# SCH-8-ESC6.net
KiCad netlist of a schematic drawn in Altium Designer
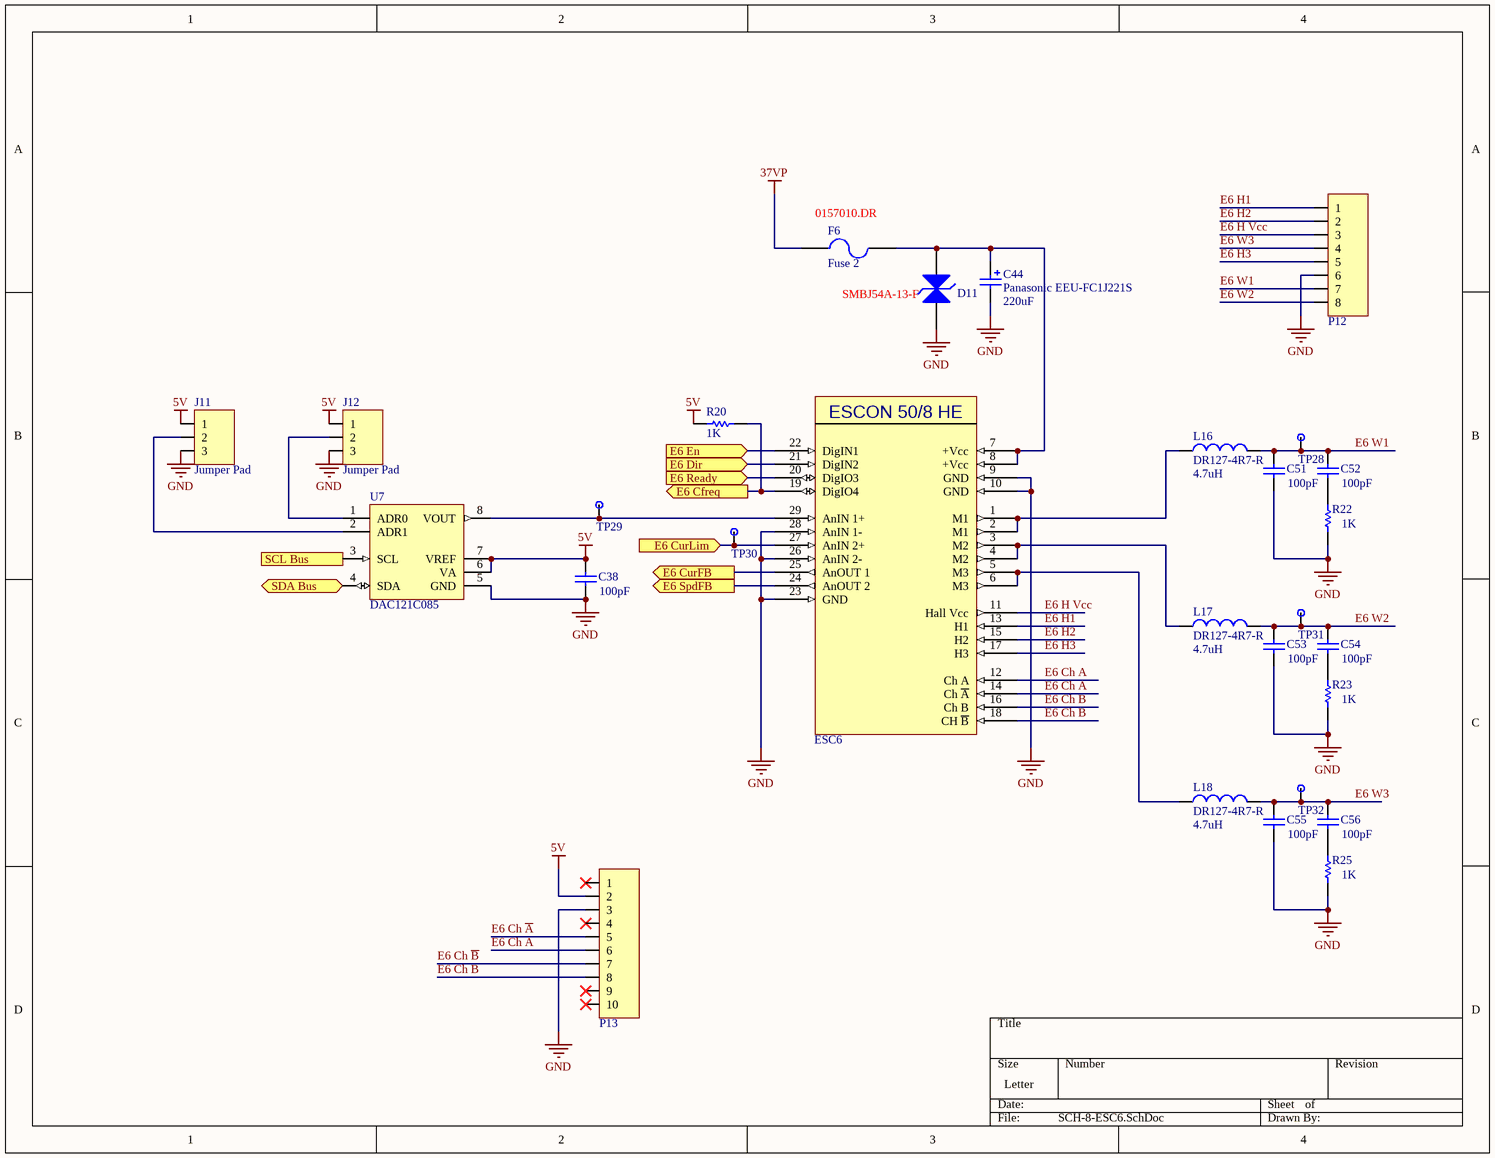
[diagram p0: SCH-8-ESC6.SchDoc]

(export (version "E")
  (design (tool "Eeschema 10.0.6"))
  (components
    (comp (ref "C38")
      (value "100pF")
      (footprint "C1206")
      (description "Capacitor (Semiconductor SIM Model)")
      (fields (field (name "Comment") "Cap Semi") (field (name "PUBLISHER") "Altium Limited"))
      (libsource (lib "Miscellaneous Devices") (part "Cap Semi"))
    )
    (comp (ref "C44")
      (value "Panasonic EEU-FC1J221S")
      (footprint "Panasonic EEU-FC1J221S")
      (description "Polarized Capacitor (Radial)")
      (fields (field (name "ALTIUM_VALUE") "220uF"))
      (libsource (lib "RSX_Capacitors") (part "Panasonic EEU-FC1J221S"))
    )
    (comp (ref "C51")
      (value "100pF")
      (footprint "C1206")
      (description "Capacitor (Semiconductor SIM Model)")
      (fields (field (name "Comment") "Cap Semi") (field (name "PUBLISHER") "Altium Limited"))
      (libsource (lib "Miscellaneous Devices") (part "Cap Semi"))
    )
    (comp (ref "C52")
      (value "100pF")
      (footprint "C1206")
      (description "Capacitor (Semiconductor SIM Model)")
      (fields (field (name "Comment") "Cap Semi") (field (name "PUBLISHER") "Altium Limited"))
      (libsource (lib "Miscellaneous Devices") (part "Cap Semi"))
    )
    (comp (ref "C53")
      (value "100pF")
      (footprint "C1206")
      (description "Capacitor (Semiconductor SIM Model)")
      (fields (field (name "Comment") "Cap Semi") (field (name "PUBLISHER") "Altium Limited"))
      (libsource (lib "Miscellaneous Devices") (part "Cap Semi"))
    )
    (comp (ref "C54")
      (value "100pF")
      (footprint "C1206")
      (description "Capacitor (Semiconductor SIM Model)")
      (fields (field (name "Comment") "Cap Semi") (field (name "PUBLISHER") "Altium Limited"))
      (libsource (lib "Miscellaneous Devices") (part "Cap Semi"))
    )
    (comp (ref "C55")
      (value "100pF")
      (footprint "C1206")
      (description "Capacitor (Semiconductor SIM Model)")
      (fields (field (name "Comment") "Cap Semi") (field (name "PUBLISHER") "Altium Limited"))
      (libsource (lib "Miscellaneous Devices") (part "Cap Semi"))
    )
    (comp (ref "C56")
      (value "100pF")
      (footprint "C1206")
      (description "Capacitor (Semiconductor SIM Model)")
      (fields (field (name "Comment") "Cap Semi") (field (name "PUBLISHER") "Altium Limited"))
      (libsource (lib "Miscellaneous Devices") (part "Cap Semi"))
    )
    (comp (ref "D11")
      (value "TVS_DIODE")
      (footprint "SMBJ54A-13-F")
      (description "TVS Diode")
      (fields (field (name "PUBLISHER") "Altium Limited"))
      (libsource (lib "RSX_Diodes") (part "TVS_DIODE"))
    )
    (comp (ref "ESC6")
      (value "ESCON 50/8 HE")
      (footprint "ESCON 50/8 HE")
      (description "ESCON Module 50/8 HE Servocontroller")
      (libsource (lib "RSX_Modules") (part "ESCON 50/8 HE"))
    )
    (comp (ref "F6")
      (value "Fuse 2")
      (footprint "0157010.DR")
      (description "Fuse")
      (fields (field (name "PUBLISHER") "Altium Limited"))
      (libsource (lib "RSX_Miscellaneous") (part "Fuse 2"))
    )
    (comp (ref "J11")
      (value "Jumper Pad")
      (footprint "3 Pad TH")
      (libsource (lib "RSX_Test_Points") (part "3 Pad Jump Sel"))
    )
    (comp (ref "J12")
      (value "Jumper Pad")
      (footprint "3 Pad TH")
      (libsource (lib "RSX_Test_Points") (part "3 Pad Jump Sel"))
    )
    (comp (ref "L16")
      (value "DR127-4R7-R")
      (footprint "DR127-4R7-R")
      (description "4.7µH Shielded Wirewound Inductor 8.25A 9.17mOhm Nonstandard")
      (fields (field (name "ALTIUM_VALUE") "4.7uH") (field (name "PUBLISHER") "Altium Limited"))
      (libsource (lib "RSX_Inductors") (part "DR127-4R7-R"))
    )
    (comp (ref "L17")
      (value "DR127-4R7-R")
      (footprint "DR127-4R7-R")
      (description "4.7µH Shielded Wirewound Inductor 8.25A 9.17mOhm Nonstandard")
      (fields (field (name "ALTIUM_VALUE") "4.7uH") (field (name "PUBLISHER") "Altium Limited"))
      (libsource (lib "RSX_Inductors") (part "DR127-4R7-R"))
    )
    (comp (ref "L18")
      (value "DR127-4R7-R")
      (footprint "DR127-4R7-R")
      (description "4.7µH Shielded Wirewound Inductor 8.25A 9.17mOhm Nonstandard")
      (fields (field (name "ALTIUM_VALUE") "4.7uH") (field (name "PUBLISHER") "Altium Limited"))
      (libsource (lib "RSX_Inductors") (part "DR127-4R7-R"))
    )
    (comp (ref "P12")
      (value "Mini-Fit Jr 8 Pos")
      (footprint "Molex Mini-Fit Jr 0039281083")
      (libsource (lib "RSX_Connectors") (part "Molex Mini-Fit Jr 8pos Vert"))
    )
    (comp (ref "P13")
      (value "Header_10_Pos_Ribbon Male")
      (footprint "3M_2510-6002UB")
      (description "3M_2510-6002UB")
      (libsource (lib "RSX_Connectors") (part "Header_10_Pos_Ribbon Male"))
    )
    (comp (ref "R20")
      (value "1K")
      (footprint "RESC1608X06N_0603")
      (description "Resistor")
      (fields (field (name "Comment") "Res1") (field (name "PUBLISHER") "Altium Limited"))
      (libsource (lib "RSX_Resistors") (part "Res1"))
    )
    (comp (ref "R22")
      (value "1K")
      (footprint "RESC1608X06N_0603")
      (description "Resistor")
      (fields (field (name "Comment") "Res1") (field (name "PUBLISHER") "Altium Limited"))
      (libsource (lib "RSX_Resistors") (part "Res1"))
    )
    (comp (ref "R23")
      (value "1K")
      (footprint "RESC1608X06N_0603")
      (description "Resistor")
      (fields (field (name "Comment") "Res1") (field (name "PUBLISHER") "Altium Limited"))
      (libsource (lib "RSX_Resistors") (part "Res1"))
    )
    (comp (ref "R25")
      (value "1K")
      (footprint "RESC1608X06N_0603")
      (description "Resistor")
      (fields (field (name "Comment") "Res1") (field (name "PUBLISHER") "Altium Limited"))
      (libsource (lib "RSX_Resistors") (part "Res1"))
    )
    (comp (ref "TP28")
      (value "TestPt")
      (footprint "50_MIL_PAD")
      (libsource (lib "RSX_Test_Points") (part "TestPt"))
    )
    (comp (ref "TP29")
      (value "TestPt")
      (footprint "50_MIL_PAD")
      (libsource (lib "RSX_Test_Points") (part "TestPt"))
    )
    (comp (ref "TP30")
      (value "TestPt")
      (footprint "50_MIL_PAD")
      (libsource (lib "RSX_Test_Points") (part "TestPt"))
    )
    (comp (ref "TP31")
      (value "TestPt")
      (footprint "50_MIL_PAD")
      (libsource (lib "RSX_Test_Points") (part "TestPt"))
    )
    (comp (ref "TP32")
      (value "TestPt")
      (footprint "50_MIL_PAD")
      (libsource (lib "RSX_Test_Points") (part "TestPt"))
    )
    (comp (ref "U7")
      (value "DAC121C085")
      (footprint "MUA08A_L")
      (fields (field (name "MANUFACTURER") "National Semiconductor"))
      (libsource (lib "RSX_Schematics") (part "DAC121C085"))
    )
  )
  (nets
    (net (code "1") (name "/E6 Cfreq") (class "Default")
      (node (ref "ESC6") (pin "19") (pinfunction "DigIO4_19") (pintype "bidirectional"))
      (node (ref "R20") (pin "1") (pinfunction "1_1") (pintype "passive"))
    )
    (net (code "2") (name "/E6 Ch A") (class "Default")
      (node (ref "ESC6") (pin "12") (pinfunction "Ch_A_12") (pintype "input"))
      (node (ref "P13") (pin "6") (pinfunction "6_6") (pintype "passive"))
    )
    (net (code "3") (name "/E6 Ch B") (class "Default")
      (node (ref "ESC6") (pin "16") (pinfunction "Ch_B_16") (pintype "input"))
      (node (ref "P13") (pin "8") (pinfunction "8_8") (pintype "passive"))
    )
    (net (code "4") (name "/E6 Ch ~{A}") (class "Default")
      (node (ref "ESC6") (pin "14") (pinfunction "Ch_~{A}_14") (pintype "input"))
      (node (ref "P13") (pin "5") (pinfunction "5_5") (pintype "passive"))
    )
    (net (code "5") (name "/E6 Ch ~{B}") (class "Default")
      (node (ref "ESC6") (pin "18") (pinfunction "CH_~{B}_18") (pintype "input"))
      (node (ref "P13") (pin "7") (pinfunction "7_7") (pintype "passive"))
    )
    (net (code "6") (name "/E6 CurFB") (class "Default")
      (node (ref "ESC6") (pin "25") (pinfunction "AnOUT_1_25") (pintype "output"))
    )
    (net (code "7") (name "/E6 CurLim") (class "Default")
      (node (ref "ESC6") (pin "27") (pinfunction "AnIN_2+_27") (pintype "input"))
      (node (ref "TP30") (pin "1") (pinfunction "1_1") (pintype "passive"))
    )
    (net (code "8") (name "/E6 Dir") (class "Default")
      (node (ref "ESC6") (pin "21") (pinfunction "DigIN2_21") (pintype "input"))
    )
    (net (code "9") (name "/E6 En") (class "Default")
      (node (ref "ESC6") (pin "22") (pinfunction "DigIN1_22") (pintype "input"))
    )
    (net (code "10") (name "/E6 H Vcc") (class "Default")
      (node (ref "ESC6") (pin "11") (pinfunction "Hall_Vcc_11") (pintype "output"))
      (node (ref "P12") (pin "3") (pinfunction "3_3") (pintype "passive"))
    )
    (net (code "11") (name "/E6 H1") (class "Default")
      (node (ref "ESC6") (pin "13") (pinfunction "H1_13") (pintype "input"))
      (node (ref "P12") (pin "1") (pinfunction "1_1") (pintype "passive"))
    )
    (net (code "12") (name "/E6 H2") (class "Default")
      (node (ref "ESC6") (pin "15") (pinfunction "H2_15") (pintype "input"))
      (node (ref "P12") (pin "2") (pinfunction "2_2") (pintype "passive"))
    )
    (net (code "13") (name "/E6 H3") (class "Default")
      (node (ref "ESC6") (pin "17") (pinfunction "H3_17") (pintype "input"))
      (node (ref "P12") (pin "5") (pinfunction "5_5") (pintype "passive"))
    )
    (net (code "14") (name "/E6 Ready") (class "Default")
      (node (ref "ESC6") (pin "20") (pinfunction "DigIO3_20") (pintype "bidirectional"))
    )
    (net (code "15") (name "/E6 SpdFB") (class "Default")
      (node (ref "ESC6") (pin "24") (pinfunction "AnOUT_2_24") (pintype "output"))
    )
    (net (code "16") (name "/E6 W1") (class "Default")
      (node (ref "C51") (pin "2") (pinfunction "2_2") (pintype "passive"))
      (node (ref "C52") (pin "2") (pinfunction "2_2") (pintype "passive"))
      (node (ref "L16") (pin "2") (pinfunction "2_2") (pintype "passive"))
      (node (ref "P12") (pin "7") (pinfunction "7_7") (pintype "passive"))
      (node (ref "TP28") (pin "1") (pinfunction "1_1") (pintype "passive"))
    )
    (net (code "17") (name "/E6 W2") (class "Default")
      (node (ref "C53") (pin "2") (pinfunction "2_2") (pintype "passive"))
      (node (ref "C54") (pin "2") (pinfunction "2_2") (pintype "passive"))
      (node (ref "L17") (pin "2") (pinfunction "2_2") (pintype "passive"))
      (node (ref "P12") (pin "8") (pinfunction "8_8") (pintype "passive"))
      (node (ref "TP31") (pin "1") (pinfunction "1_1") (pintype "passive"))
    )
    (net (code "18") (name "/E6 W3") (class "Default")
      (node (ref "C55") (pin "2") (pinfunction "2_2") (pintype "passive"))
      (node (ref "C56") (pin "2") (pinfunction "2_2") (pintype "passive"))
      (node (ref "L18") (pin "2") (pinfunction "2_2") (pintype "passive"))
      (node (ref "P12") (pin "4") (pinfunction "4_4") (pintype "passive"))
      (node (ref "TP32") (pin "1") (pinfunction "1_1") (pintype "passive"))
    )
    (net (code "19") (name "/SCL Bus") (class "Default")
      (node (ref "U7") (pin "3") (pinfunction "SCL_3") (pintype "input"))
    )
    (net (code "20") (name "/SDA Bus") (class "Default")
      (node (ref "U7") (pin "4") (pinfunction "SDA_4") (pintype "bidirectional"))
    )
    (net (code "21") (name "5V") (class "Default")
      (node (ref "C38") (pin "2") (pinfunction "2_2") (pintype "passive"))
      (node (ref "J11") (pin "1") (pinfunction "1_1") (pintype "passive"))
      (node (ref "J12") (pin "1") (pinfunction "1_1") (pintype "passive"))
      (node (ref "P13") (pin "2") (pinfunction "2_2") (pintype "passive"))
      (node (ref "R20") (pin "2") (pinfunction "2_2") (pintype "passive"))
      (node (ref "U7") (pin "6") (pinfunction "VA_6") (pintype "power_in"))
      (node (ref "U7") (pin "7") (pinfunction "VREF_7") (pintype "power_in"))
    )
    (net (code "22") (name "37VP") (class "Default")
      (node (ref "F6") (pin "1") (pinfunction "1_1") (pintype "passive"))
    )
    (net (code "23") (name "GND") (class "Default")
      (node (ref "C38") (pin "1") (pinfunction "1_1") (pintype "passive"))
      (node (ref "C44") (pin "2") (pinfunction "2_2") (pintype "passive"))
      (node (ref "C51") (pin "1") (pinfunction "1_1") (pintype "passive"))
      (node (ref "C53") (pin "1") (pinfunction "1_1") (pintype "passive"))
      (node (ref "C55") (pin "1") (pinfunction "1_1") (pintype "passive"))
      (node (ref "D11") (pin "1") (pinfunction "A_1") (pintype "passive"))
      (node (ref "ESC6") (pin "10") (pinfunction "GND_10") (pintype "input"))
      (node (ref "ESC6") (pin "23") (pinfunction "GND_23") (pintype "input"))
      (node (ref "ESC6") (pin "26") (pinfunction "AnIN_2-_26") (pintype "input"))
      (node (ref "ESC6") (pin "28") (pinfunction "AnIN_1-_28") (pintype "input"))
      (node (ref "ESC6") (pin "9") (pinfunction "GND_9") (pintype "input"))
      (node (ref "J11") (pin "3") (pinfunction "3_3") (pintype "passive"))
      (node (ref "J12") (pin "3") (pinfunction "3_3") (pintype "passive"))
      (node (ref "P12") (pin "6") (pinfunction "6_6") (pintype "passive"))
      (node (ref "P13") (pin "3") (pinfunction "3_3") (pintype "passive"))
      (node (ref "R22") (pin "1") (pinfunction "1_1") (pintype "passive"))
      (node (ref "R23") (pin "1") (pinfunction "1_1") (pintype "passive"))
      (node (ref "R25") (pin "1") (pinfunction "1_1") (pintype "passive"))
      (node (ref "U7") (pin "5") (pinfunction "GND_5") (pintype "power_in"))
    )
    (net (code "24") (name "Net-(C52-Pad1)") (class "Default")
      (node (ref "C52") (pin "1") (pinfunction "1_1") (pintype "passive"))
      (node (ref "R22") (pin "2") (pinfunction "2_2") (pintype "passive"))
    )
    (net (code "25") (name "Net-(C54-Pad1)") (class "Default")
      (node (ref "C54") (pin "1") (pinfunction "1_1") (pintype "passive"))
      (node (ref "R23") (pin "2") (pinfunction "2_2") (pintype "passive"))
    )
    (net (code "26") (name "Net-(C56-Pad1)") (class "Default")
      (node (ref "C56") (pin "1") (pinfunction "1_1") (pintype "passive"))
      (node (ref "R25") (pin "2") (pinfunction "2_2") (pintype "passive"))
    )
    (net (code "27") (name "Net-(D11-K)") (class "Default")
      (node (ref "C44") (pin "1") (pinfunction "1_1") (pintype "passive"))
      (node (ref "D11") (pin "2") (pinfunction "K_2") (pintype "passive"))
      (node (ref "ESC6") (pin "7") (pinfunction "+Vcc_7") (pintype "input"))
      (node (ref "ESC6") (pin "8") (pinfunction "+Vcc_8") (pintype "input"))
      (node (ref "F6") (pin "2") (pinfunction "2_2") (pintype "passive"))
    )
    (net (code "28") (name "Net-(ESC6-AnIN_1+)") (class "Default")
      (node (ref "ESC6") (pin "29") (pinfunction "AnIN_1+_29") (pintype "input"))
      (node (ref "TP29") (pin "1") (pinfunction "1_1") (pintype "passive"))
      (node (ref "U7") (pin "8") (pinfunction "VOUT_8") (pintype "output"))
    )
    (net (code "29") (name "Net-(ESC6-M1-Pad1)") (class "Default")
      (node (ref "ESC6") (pin "1") (pinfunction "M1_1") (pintype "output"))
      (node (ref "ESC6") (pin "2") (pinfunction "M1_2") (pintype "output"))
      (node (ref "L16") (pin "1") (pinfunction "1_1") (pintype "passive"))
    )
    (net (code "30") (name "Net-(ESC6-M2-Pad3)") (class "Default")
      (node (ref "ESC6") (pin "3") (pinfunction "M2_3") (pintype "output"))
      (node (ref "ESC6") (pin "4") (pinfunction "M2_4") (pintype "output"))
      (node (ref "L17") (pin "1") (pinfunction "1_1") (pintype "passive"))
    )
    (net (code "31") (name "Net-(ESC6-M3-Pad5)") (class "Default")
      (node (ref "ESC6") (pin "5") (pinfunction "M3_5") (pintype "output"))
      (node (ref "ESC6") (pin "6") (pinfunction "M3_6") (pintype "output"))
      (node (ref "L18") (pin "1") (pinfunction "1_1") (pintype "passive"))
    )
    (net (code "32") (name "Net-(U7-ADR0)") (class "Default")
      (node (ref "J12") (pin "2") (pinfunction "2_2") (pintype "passive"))
      (node (ref "U7") (pin "1") (pinfunction "ADR0_1") (pintype "tri_state"))
    )
    (net (code "33") (name "Net-(U7-ADR1)") (class "Default")
      (node (ref "J11") (pin "2") (pinfunction "2_2") (pintype "passive"))
      (node (ref "U7") (pin "2") (pinfunction "ADR1_2") (pintype "tri_state"))
    )
    (net (code "34") (name "unconnected-(P13-Pad1)") (class "Default")
      (node (ref "P13") (pin "1") (pinfunction "1_1") (pintype "passive+no_connect"))
    )
    (net (code "35") (name "unconnected-(P13-Pad4)") (class "Default")
      (node (ref "P13") (pin "4") (pinfunction "4_4") (pintype "passive+no_connect"))
    )
    (net (code "36") (name "unconnected-(P13-Pad9)") (class "Default")
      (node (ref "P13") (pin "9") (pinfunction "9_9") (pintype "passive+no_connect"))
    )
    (net (code "37") (name "unconnected-(P13-Pad10)") (class "Default")
      (node (ref "P13") (pin "10") (pinfunction "10_10") (pintype "passive+no_connect"))
    )
  )
)
